# Sheet1.net
KiCad netlist of a schematic drawn in Altium Designer
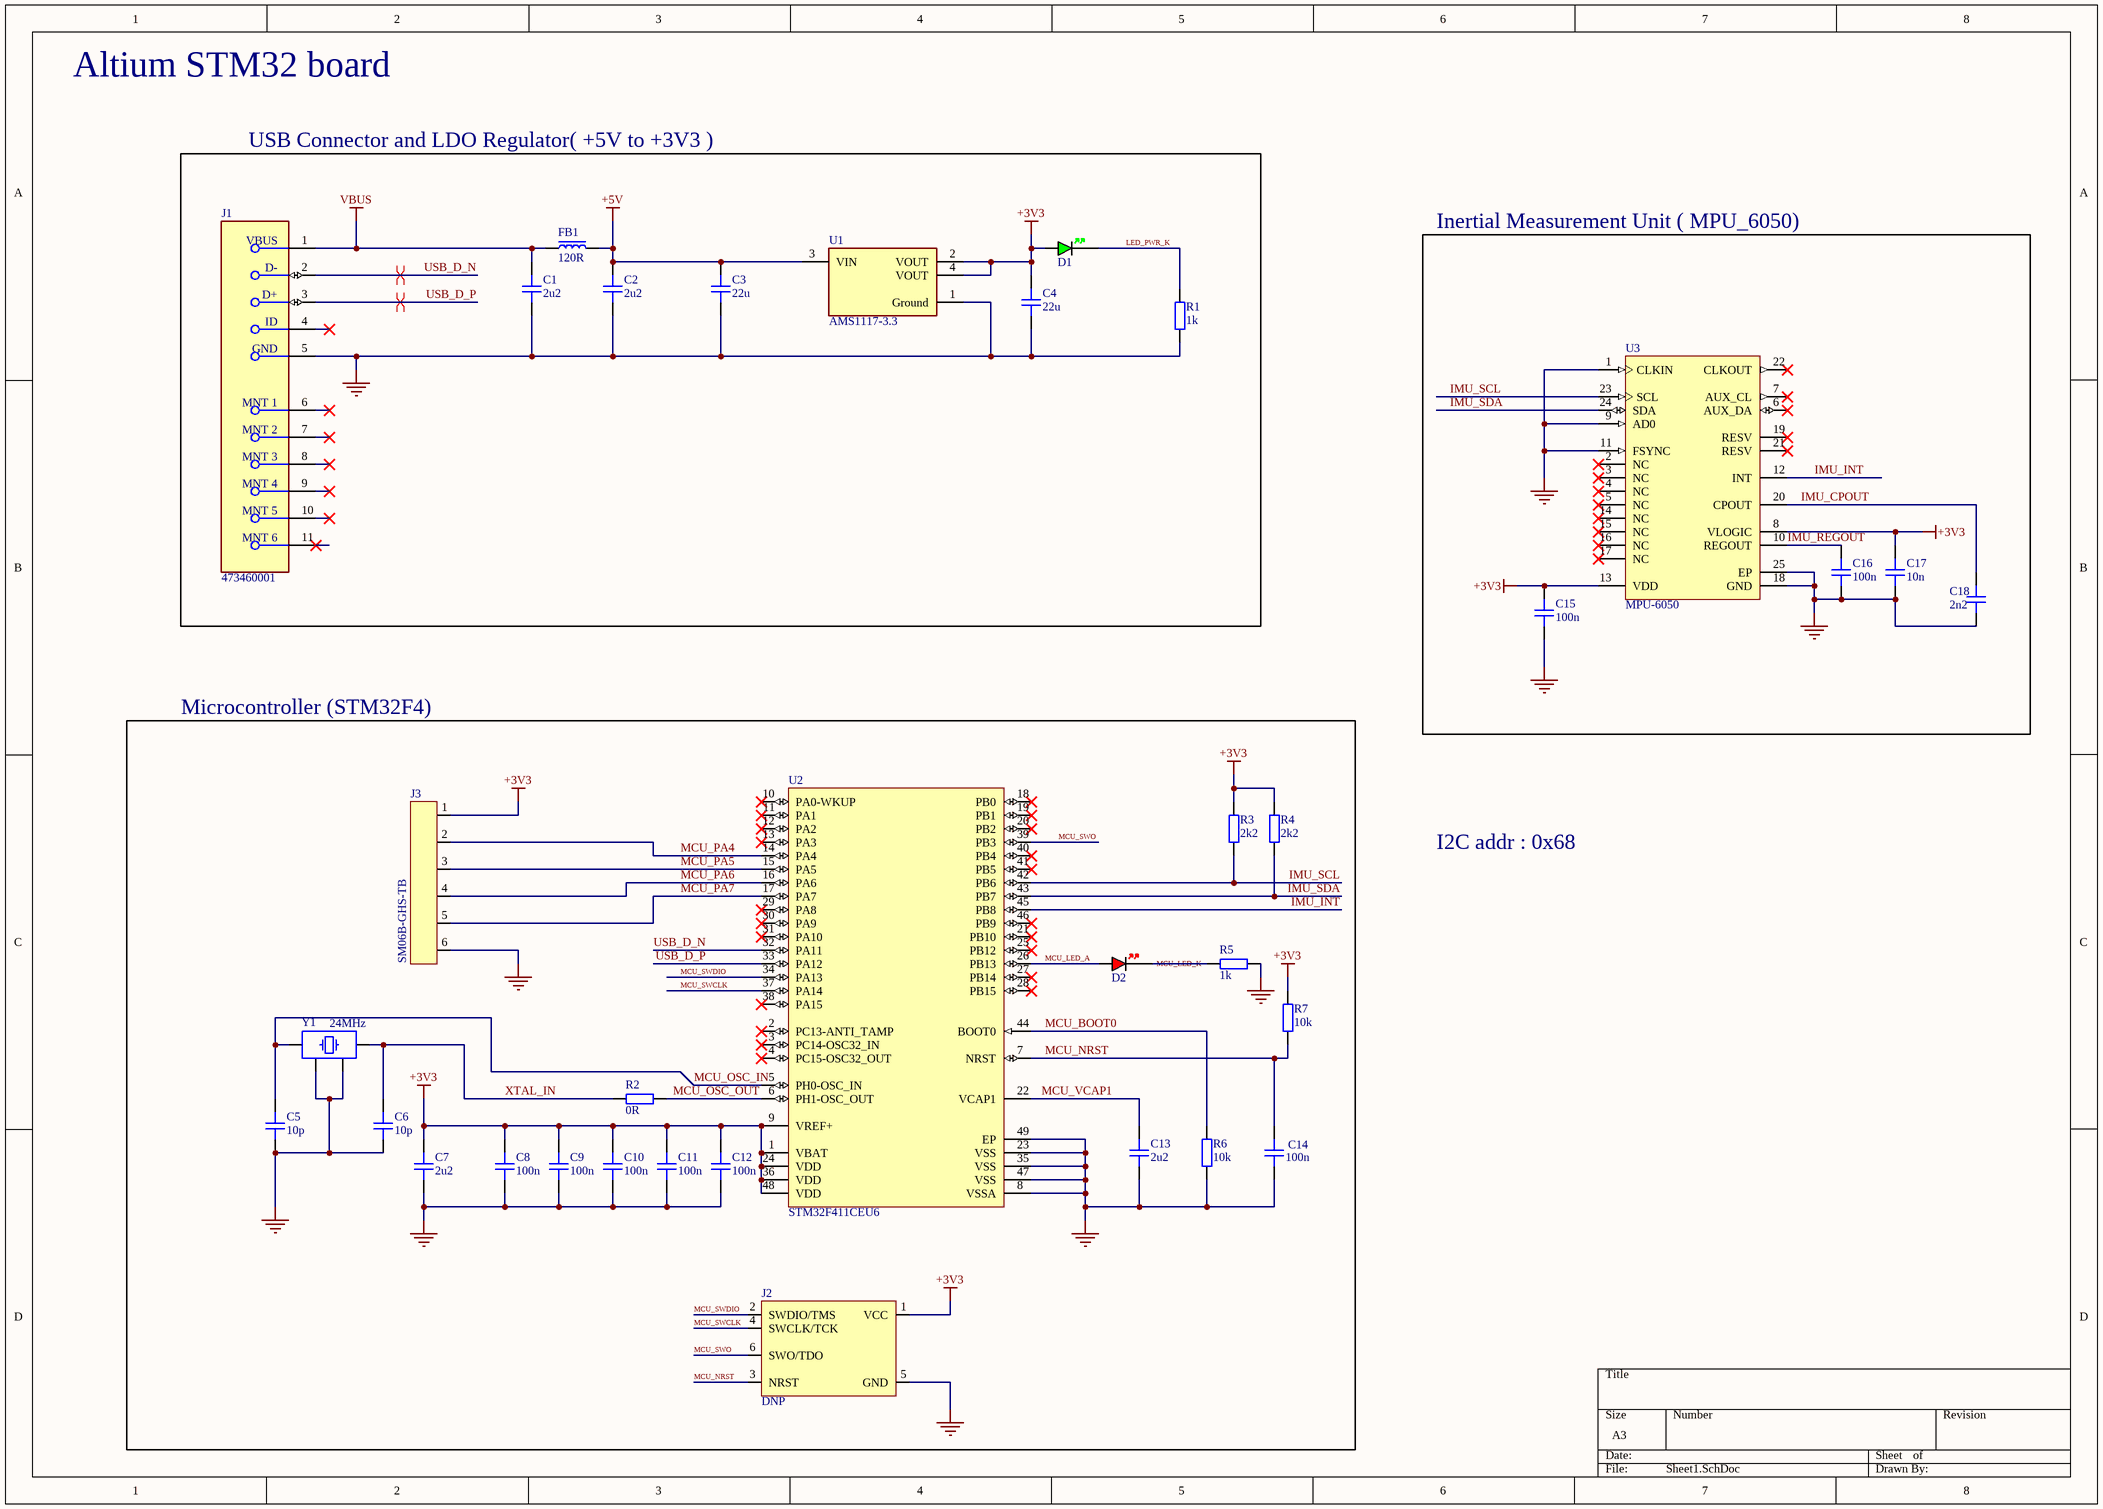
[diagram p0: Sheet1.SchDoc]

(export (version "E")
  (design (tool "Eeschema 10.0.6"))
  (components
    (comp (ref "C1")
      (value "2u2")
      (footprint "CAP_0603")
      (description "Capacitor SMD 0603")
      (libsource (lib "Schematic-Lib-PhilsLab") (part "CAP_0603"))
    )
    (comp (ref "C2")
      (value "2u2")
      (footprint "CAP_0603")
      (description "Capacitor SMD 0603")
      (libsource (lib "Schematic-Lib-PhilsLab") (part "CAP_0603"))
    )
    (comp (ref "C3")
      (value "22u")
      (footprint "CAP_0805")
      (description "Capacitor SMD 0805")
      (libsource (lib "Schematic-Lib-PhilsLab") (part "CAP_0805"))
    )
    (comp (ref "C4")
      (value "22u")
      (footprint "CAP_0805")
      (description "Capacitor SMD 0805")
      (libsource (lib "Schematic-Lib-PhilsLab") (part "CAP_0805"))
    )
    (comp (ref "C5")
      (value "10p")
      (footprint "CAP_0402")
      (description "Capacitor SMD 0402")
      (libsource (lib "Schematic-Lib-PhilsLab") (part "CAP_0402"))
    )
    (comp (ref "C6")
      (value "10p")
      (footprint "CAP_0402")
      (description "Capacitor SMD 0402")
      (libsource (lib "Schematic-Lib-PhilsLab") (part "CAP_0402"))
    )
    (comp (ref "C7")
      (value "2u2")
      (footprint "CAP_0603")
      (description "Capacitor SMD 0603")
      (libsource (lib "Schematic-Lib-PhilsLab") (part "CAP_0603"))
    )
    (comp (ref "C8")
      (value "100n")
      (footprint "CAP_0402")
      (description "Capacitor SMD 0402")
      (libsource (lib "Schematic-Lib-PhilsLab") (part "CAP_0402"))
    )
    (comp (ref "C9")
      (value "100n")
      (footprint "CAP_0402")
      (description "Capacitor SMD 0402")
      (libsource (lib "Schematic-Lib-PhilsLab") (part "CAP_0402"))
    )
    (comp (ref "C10")
      (value "100n")
      (footprint "CAP_0402")
      (description "Capacitor SMD 0402")
      (libsource (lib "Schematic-Lib-PhilsLab") (part "CAP_0402"))
    )
    (comp (ref "C11")
      (value "100n")
      (footprint "CAP_0402")
      (description "Capacitor SMD 0402")
      (libsource (lib "Schematic-Lib-PhilsLab") (part "CAP_0402"))
    )
    (comp (ref "C12")
      (value "100n")
      (footprint "CAP_0402")
      (description "Capacitor SMD 0402")
      (libsource (lib "Schematic-Lib-PhilsLab") (part "CAP_0402"))
    )
    (comp (ref "C13")
      (value "2u2")
      (footprint "CAP_0603")
      (description "Capacitor SMD 0603")
      (libsource (lib "Schematic-Lib-PhilsLab") (part "CAP_0603"))
    )
    (comp (ref "C14")
      (value "100n")
      (footprint "CAP_0402")
      (description "Capacitor SMD 0402")
      (libsource (lib "Schematic-Lib-PhilsLab") (part "CAP_0402"))
    )
    (comp (ref "C15")
      (value "100n")
      (footprint "CAP_0402")
      (description "Capacitor SMD 0402")
      (libsource (lib "Schematic-Lib-PhilsLab") (part "CAP_0402"))
    )
    (comp (ref "C16")
      (value "100n")
      (footprint "CAP_0402")
      (description "Capacitor SMD 0402")
      (libsource (lib "Schematic-Lib-PhilsLab") (part "CAP_0402"))
    )
    (comp (ref "C17")
      (value "10n")
      (footprint "CAP_0402")
      (description "Capacitor SMD 0402")
      (libsource (lib "Schematic-Lib-PhilsLab") (part "CAP_0402"))
    )
    (comp (ref "C18")
      (value "2n2")
      (footprint "CAP_0402")
      (description "Capacitor SMD 0402")
      (libsource (lib "Schematic-Lib-PhilsLab") (part "CAP_0402"))
    )
    (comp (ref "D1")
      (value "GREEN")
      (footprint "LED_0402_GREEN")
      (description "LED 0402 GREEN SMD")
      (libsource (lib "Schematic-Lib-PhilsLab") (part "LED_0402_GREEN"))
    )
    (comp (ref "D2")
      (value "RED")
      (footprint "LED_0402_RED")
      (description "LED 0402 RED SMD")
      (libsource (lib "Schematic-Lib-PhilsLab") (part "LED_0402_RED"))
    )
    (comp (ref "FB1")
      (value "120R")
      (footprint "FB_0603")
      (description "Ferrite Bead SMD 0603")
      (libsource (lib "Schematic-Lib-PhilsLab") (part "FB_0603"))
    )
    (comp (ref "J1")
      (value "473460001")
      (footprint "FP-473460001-MFG")
      (description "CONN RCPT USB2.0 MICRO B SMD R/A")
      (fields
        (field (name "OCTOPART") "https://octopart.com/47346-0001-molex-7164928")
        (field (name "MANUFACTURER") "Molex")
      )
      (libsource (lib "Altium Content Vault") (part "53ae1f1d9b557310b43ca686e5bb76a"))
    )
    (comp (ref "J2")
      (value "DNP")
      (footprint "TC2030-NL-FP")
      (description "Tag-Connect No-Solder SWD Debug Connector (No Legs) DO NOT PLACE")
      (fields
        (field (name "MANUFACTURER") "Tag-Connect")
        (field (name "MANUFACTURER PART NUMBER") "TC2030-NL-FP")
      )
      (libsource (lib "Schematic-Lib-PhilsLab") (part "TC2030-NL"))
    )
    (comp (ref "J3")
      (value "SM06B-GHS-TB")
      (footprint "SM06B-GHS-TB")
      (description "Header Connector 6 Position 1.25MM Pitch SMD Horizontal JST GH")
      (fields (field (name "MANUFACTURER") "JST"))
      (libsource (lib "Schematic-Lib-PhilsLab") (part "SM06B-GHS-TB"))
    )
    (comp (ref "R1")
      (value "1k")
      (footprint "RES_0402")
      (description "Resistor SMD 0402")
      (libsource (lib "Schematic-Lib-PhilsLab") (part "RES_0402"))
    )
    (comp (ref "R2")
      (value "0R")
      (footprint "RES_0402")
      (description "Resistor SMD 0402")
      (libsource (lib "Schematic-Lib-PhilsLab") (part "RES_0402"))
    )
    (comp (ref "R3")
      (value "2k2")
      (footprint "RES_0402")
      (description "Resistor SMD 0402")
      (libsource (lib "Schematic-Lib-PhilsLab") (part "RES_0402"))
    )
    (comp (ref "R4")
      (value "2k2")
      (footprint "RES_0402")
      (description "Resistor SMD 0402")
      (libsource (lib "Schematic-Lib-PhilsLab") (part "RES_0402"))
    )
    (comp (ref "R5")
      (value "1k")
      (footprint "RES_0402")
      (description "Resistor SMD 0402")
      (libsource (lib "Schematic-Lib-PhilsLab") (part "RES_0402"))
    )
    (comp (ref "R6")
      (value "10k")
      (footprint "RES_0402")
      (description "Resistor SMD 0402")
      (libsource (lib "Schematic-Lib-PhilsLab") (part "RES_0402"))
    )
    (comp (ref "R7")
      (value "10k")
      (footprint "RES_0402")
      (description "Resistor SMD 0402")
      (libsource (lib "Schematic-Lib-PhilsLab") (part "RES_0402"))
    )
    (comp (ref "U1")
      (value "AMS1117-3.3")
      (footprint "FP-AMS1117-IPC_C")
      (description "LDO Voltage Regulators 1A, 3.3V")
      (fields
        (field (name "OCTOPART") "https://octopart.com/ams1117-3.3-advanced+monolithic+systems-25899300")
        (field (name "MANUFACTURER") "Advanced Monolithic Systems")
      )
      (libsource (lib "Altium Content Vault") (part "8bdbb5f8e77002000e30dd2845d0354"))
    )
    (comp (ref "U2")
      (value "STM32F411CEU6")
      (footprint "STM-UFQFPN48_L")
      (libsource (lib "Altium Content Vault") (part "MC-ARM-STM32F411-UFQFPN48"))
    )
    (comp (ref "U3")
      (value "MPU-6050")
      (footprint "IS-QFN-24_V")
      (fields (field (name "MANUFACTURER") "InvenSense"))
      (libsource (lib "Altium Content Vault") (part "IS-MPU-6050-QFN-24"))
    )
    (comp (ref "Y1")
      (value "24MHz")
      (footprint "XTAL_3225")
      (description "Crystal SMD 24MHz 10PPM 7pF 3225")
      (fields
        (field (name "MANUFACTURER") "Epson")
        (field (name "MANUFACTURER PART NUMBER") "TSX-3225 24.0000MF15X-AC")
      )
      (libsource (lib "Schematic-Lib-PhilsLab") (part "TSX-3225_24.0000MF15X-AC"))
    )
  )
  (nets
    (net (code "1") (name "+3V3") (class "Default")
      (node (ref "C10") (pin "2") (pinfunction "2_2") (pintype "passive"))
      (node (ref "C11") (pin "2") (pinfunction "2_2") (pintype "passive"))
      (node (ref "C12") (pin "2") (pinfunction "2_2") (pintype "passive"))
      (node (ref "C15") (pin "2") (pinfunction "2_2") (pintype "passive"))
      (node (ref "C17") (pin "2") (pinfunction "2_2") (pintype "passive"))
      (node (ref "C4") (pin "2") (pinfunction "2_2") (pintype "passive"))
      (node (ref "C7") (pin "2") (pinfunction "2_2") (pintype "passive"))
      (node (ref "C8") (pin "2") (pinfunction "2_2") (pintype "passive"))
      (node (ref "C9") (pin "2") (pinfunction "2_2") (pintype "passive"))
      (node (ref "D1") (pin "A") (pinfunction "A_A") (pintype "passive"))
      (node (ref "J2") (pin "1") (pinfunction "VCC_1") (pintype "passive"))
      (node (ref "J3") (pin "1") (pinfunction "1_1") (pintype "passive"))
      (node (ref "R3") (pin "2") (pinfunction "2_2") (pintype "passive"))
      (node (ref "R4") (pin "2") (pinfunction "2_2") (pintype "passive"))
      (node (ref "R7") (pin "2") (pinfunction "2_2") (pintype "passive"))
      (node (ref "U1") (pin "2") (pinfunction "VOUT_2") (pintype "passive"))
      (node (ref "U1") (pin "4") (pinfunction "VOUT_4") (pintype "passive"))
      (node (ref "U2") (pin "1") (pinfunction "VBAT_1") (pintype "power_in"))
      (node (ref "U2") (pin "24") (pinfunction "VDD_24") (pintype "power_in"))
      (node (ref "U2") (pin "36") (pinfunction "VDD_36") (pintype "power_in"))
      (node (ref "U2") (pin "48") (pinfunction "VDD_48") (pintype "power_in"))
      (node (ref "U2") (pin "9") (pinfunction "VREF+_9") (pintype "power_in"))
      (node (ref "U3") (pin "13") (pinfunction "VDD_13") (pintype "power_in"))
      (node (ref "U3") (pin "8") (pinfunction "VLOGIC_8") (pintype "power_in"))
    )
    (net (code "2") (name "+5V") (class "Default")
      (node (ref "C2") (pin "2") (pinfunction "2_2") (pintype "passive"))
      (node (ref "C3") (pin "2") (pinfunction "2_2") (pintype "passive"))
      (node (ref "FB1") (pin "2") (pinfunction "2_2") (pintype "passive"))
      (node (ref "U1") (pin "3") (pinfunction "VIN_3") (pintype "power_in"))
    )
    (net (code "3") (name "/IMU_CPOUT") (class "Default")
      (node (ref "C18") (pin "2") (pinfunction "2_2") (pintype "passive"))
      (node (ref "U3") (pin "20") (pinfunction "CPOUT_20") (pintype "passive"))
    )
    (net (code "4") (name "/IMU_INT") (class "Default")
      (node (ref "U2") (pin "45") (pinfunction "PB8_45") (pintype "bidirectional"))
      (node (ref "U3") (pin "12") (pinfunction "INT_12") (pintype "open_collector"))
    )
    (net (code "5") (name "/IMU_REGOUT") (class "Default")
      (node (ref "C16") (pin "2") (pinfunction "2_2") (pintype "passive"))
      (node (ref "U3") (pin "10") (pinfunction "REGOUT_10") (pintype "passive"))
    )
    (net (code "6") (name "/IMU_SCL") (class "Default")
      (node (ref "R3") (pin "1") (pinfunction "1_1") (pintype "passive"))
      (node (ref "U2") (pin "42") (pinfunction "PB6_42") (pintype "bidirectional"))
      (node (ref "U3") (pin "23") (pinfunction "SCL_23") (pintype "input"))
    )
    (net (code "7") (name "/IMU_SDA") (class "Default")
      (node (ref "R4") (pin "1") (pinfunction "1_1") (pintype "passive"))
      (node (ref "U2") (pin "43") (pinfunction "PB7_43") (pintype "bidirectional"))
      (node (ref "U3") (pin "24") (pinfunction "SDA_24") (pintype "bidirectional"))
    )
    (net (code "8") (name "/LED_PWR_K") (class "Default")
      (node (ref "D1") (pin "K") (pinfunction "K_K") (pintype "passive"))
      (node (ref "R1") (pin "2") (pinfunction "2_2") (pintype "passive"))
    )
    (net (code "9") (name "/MCU_BOOT0") (class "Default")
      (node (ref "R6") (pin "2") (pinfunction "2_2") (pintype "passive"))
      (node (ref "U2") (pin "44") (pinfunction "BOOT0_44") (pintype "input"))
    )
    (net (code "10") (name "/MCU_LED_A") (class "Default")
      (node (ref "D2") (pin "A") (pinfunction "A_A") (pintype "passive"))
      (node (ref "U2") (pin "26") (pinfunction "PB13_26") (pintype "bidirectional"))
    )
    (net (code "11") (name "/MCU_LED_K") (class "Default")
      (node (ref "D2") (pin "K") (pinfunction "K_K") (pintype "passive"))
      (node (ref "R5") (pin "2") (pinfunction "2_2") (pintype "passive"))
    )
    (net (code "12") (name "/MCU_NRST") (class "Default")
      (node (ref "C14") (pin "2") (pinfunction "2_2") (pintype "passive"))
      (node (ref "J2") (pin "3") (pinfunction "NRST_3") (pintype "passive"))
      (node (ref "R7") (pin "1") (pinfunction "1_1") (pintype "passive"))
      (node (ref "U2") (pin "7") (pinfunction "NRST_7") (pintype "bidirectional"))
    )
    (net (code "13") (name "/MCU_OSC_IN") (class "Default")
      (node (ref "C5") (pin "2") (pinfunction "2_2") (pintype "passive"))
      (node (ref "U2") (pin "5") (pinfunction "PH0-OSC_IN_5") (pintype "bidirectional"))
      (node (ref "Y1") (pin "1") (pinfunction "1_1") (pintype "passive"))
    )
    (net (code "14") (name "/MCU_OSC_OUT") (class "Default")
      (node (ref "R2") (pin "2") (pinfunction "2_2") (pintype "passive"))
      (node (ref "U2") (pin "6") (pinfunction "PH1-OSC_OUT_6") (pintype "bidirectional"))
    )
    (net (code "15") (name "/MCU_PA4") (class "Default")
      (node (ref "J3") (pin "2") (pinfunction "2_2") (pintype "passive"))
      (node (ref "U2") (pin "14") (pinfunction "PA4_14") (pintype "bidirectional"))
    )
    (net (code "16") (name "/MCU_PA5") (class "Default")
      (node (ref "J3") (pin "3") (pinfunction "3_3") (pintype "passive"))
      (node (ref "U2") (pin "15") (pinfunction "PA5_15") (pintype "bidirectional"))
    )
    (net (code "17") (name "/MCU_PA6") (class "Default")
      (node (ref "J3") (pin "4") (pinfunction "4_4") (pintype "passive"))
      (node (ref "U2") (pin "16") (pinfunction "PA6_16") (pintype "bidirectional"))
    )
    (net (code "18") (name "/MCU_PA7") (class "Default")
      (node (ref "J3") (pin "5") (pinfunction "5_5") (pintype "passive"))
      (node (ref "U2") (pin "17") (pinfunction "PA7_17") (pintype "bidirectional"))
    )
    (net (code "19") (name "/MCU_SWCLK") (class "Default")
      (node (ref "J2") (pin "4") (pinfunction "SWCLK/TCK_4") (pintype "passive"))
      (node (ref "U2") (pin "37") (pinfunction "PA14_37") (pintype "bidirectional"))
    )
    (net (code "20") (name "/MCU_SWDIO") (class "Default")
      (node (ref "J2") (pin "2") (pinfunction "SWDIO/TMS_2") (pintype "passive"))
      (node (ref "U2") (pin "34") (pinfunction "PA13_34") (pintype "bidirectional"))
    )
    (net (code "21") (name "/MCU_SWO") (class "Default")
      (node (ref "J2") (pin "6") (pinfunction "SWO/TDO_6") (pintype "passive"))
      (node (ref "U2") (pin "39") (pinfunction "PB3_39") (pintype "bidirectional"))
    )
    (net (code "22") (name "/MCU_VCAP1") (class "Default")
      (node (ref "C13") (pin "2") (pinfunction "2_2") (pintype "passive"))
      (node (ref "U2") (pin "22") (pinfunction "VCAP1_22") (pintype "passive"))
    )
    (net (code "23") (name "/USB_D_N") (class "Default")
      (node (ref "J1") (pin "2") (pinfunction "D-_2") (pintype "bidirectional"))
      (node (ref "U2") (pin "32") (pinfunction "PA11_32") (pintype "bidirectional"))
    )
    (net (code "24") (name "/USB_D_P") (class "Default")
      (node (ref "J1") (pin "3") (pinfunction "D+_3") (pintype "bidirectional"))
      (node (ref "U2") (pin "33") (pinfunction "PA12_33") (pintype "bidirectional"))
    )
    (net (code "25") (name "/XTAL_IN") (class "Default")
      (node (ref "C6") (pin "2") (pinfunction "2_2") (pintype "passive"))
      (node (ref "R2") (pin "1") (pinfunction "1_1") (pintype "passive"))
      (node (ref "Y1") (pin "3") (pinfunction "3_3") (pintype "passive"))
    )
    (net (code "26") (name "GND") (class "Default")
      (node (ref "C1") (pin "1") (pinfunction "1_1") (pintype "passive"))
      (node (ref "C10") (pin "1") (pinfunction "1_1") (pintype "passive"))
      (node (ref "C11") (pin "1") (pinfunction "1_1") (pintype "passive"))
      (node (ref "C12") (pin "1") (pinfunction "1_1") (pintype "passive"))
      (node (ref "C13") (pin "1") (pinfunction "1_1") (pintype "passive"))
      (node (ref "C14") (pin "1") (pinfunction "1_1") (pintype "passive"))
      (node (ref "C15") (pin "1") (pinfunction "1_1") (pintype "passive"))
      (node (ref "C16") (pin "1") (pinfunction "1_1") (pintype "passive"))
      (node (ref "C17") (pin "1") (pinfunction "1_1") (pintype "passive"))
      (node (ref "C18") (pin "1") (pinfunction "1_1") (pintype "passive"))
      (node (ref "C2") (pin "1") (pinfunction "1_1") (pintype "passive"))
      (node (ref "C3") (pin "1") (pinfunction "1_1") (pintype "passive"))
      (node (ref "C4") (pin "1") (pinfunction "1_1") (pintype "passive"))
      (node (ref "C5") (pin "1") (pinfunction "1_1") (pintype "passive"))
      (node (ref "C6") (pin "1") (pinfunction "1_1") (pintype "passive"))
      (node (ref "C7") (pin "1") (pinfunction "1_1") (pintype "passive"))
      (node (ref "C8") (pin "1") (pinfunction "1_1") (pintype "passive"))
      (node (ref "C9") (pin "1") (pinfunction "1_1") (pintype "passive"))
      (node (ref "J1") (pin "5") (pinfunction "GND_5") (pintype "power_in"))
      (node (ref "J2") (pin "5") (pinfunction "GND_5") (pintype "passive"))
      (node (ref "J3") (pin "6") (pinfunction "6_6") (pintype "passive"))
      (node (ref "R1") (pin "1") (pinfunction "1_1") (pintype "passive"))
      (node (ref "R5") (pin "1") (pinfunction "1_1") (pintype "passive"))
      (node (ref "R6") (pin "1") (pinfunction "1_1") (pintype "passive"))
      (node (ref "U1") (pin "1") (pinfunction "Ground_1") (pintype "power_in"))
      (node (ref "U2") (pin "23") (pinfunction "VSS_23") (pintype "power_in"))
      (node (ref "U2") (pin "35") (pinfunction "VSS_35") (pintype "power_in"))
      (node (ref "U2") (pin "47") (pinfunction "VSS_47") (pintype "power_in"))
      (node (ref "U2") (pin "49") (pinfunction "EP_49") (pintype "power_in"))
      (node (ref "U2") (pin "8") (pinfunction "VSSA_8") (pintype "power_in"))
      (node (ref "U3") (pin "1") (pinfunction "CLKIN_1") (pintype "input"))
      (node (ref "U3") (pin "11") (pinfunction "FSYNC_11") (pintype "input"))
      (node (ref "U3") (pin "18") (pinfunction "GND_18") (pintype "power_in"))
      (node (ref "U3") (pin "25") (pinfunction "EP_25") (pintype "power_in"))
      (node (ref "U3") (pin "9") (pinfunction "AD0_9") (pintype "input"))
      (node (ref "Y1") (pin "2") (pinfunction "2_2") (pintype "passive"))
      (node (ref "Y1") (pin "4") (pinfunction "4_4") (pintype "passive"))
    )
    (net (code "27") (name "VBUS") (class "Default")
      (node (ref "C1") (pin "2") (pinfunction "2_2") (pintype "passive"))
      (node (ref "FB1") (pin "1") (pinfunction "1_1") (pintype "passive"))
      (node (ref "J1") (pin "1") (pinfunction "VBUS_1") (pintype "power_in"))
    )
    (net (code "28") (name "unconnected-(J1-ID-Pad4)") (class "Default")
      (node (ref "J1") (pin "4") (pinfunction "ID_4") (pintype "passive+no_connect"))
    )
    (net (code "29") (name "unconnected-(J1-MNT_1-Pad6)") (class "Default")
      (node (ref "J1") (pin "6") (pinfunction "MNT_1_6") (pintype "passive+no_connect"))
    )
    (net (code "30") (name "unconnected-(J1-MNT_2-Pad7)") (class "Default")
      (node (ref "J1") (pin "7") (pinfunction "MNT_2_7") (pintype "passive+no_connect"))
    )
    (net (code "31") (name "unconnected-(J1-MNT_3-Pad8)") (class "Default")
      (node (ref "J1") (pin "8") (pinfunction "MNT_3_8") (pintype "passive+no_connect"))
    )
    (net (code "32") (name "unconnected-(J1-MNT_4-Pad9)") (class "Default")
      (node (ref "J1") (pin "9") (pinfunction "MNT_4_9") (pintype "passive+no_connect"))
    )
    (net (code "33") (name "unconnected-(J1-MNT_5-Pad10)") (class "Default")
      (node (ref "J1") (pin "10") (pinfunction "MNT_5_10") (pintype "passive+no_connect"))
    )
    (net (code "34") (name "unconnected-(J1-MNT_6-Pad11)") (class "Default")
      (node (ref "J1") (pin "11") (pinfunction "MNT_6_11") (pintype "passive+no_connect"))
    )
    (net (code "35") (name "unconnected-(U2-PA0-WKUP-Pad10)") (class "Default")
      (node (ref "U2") (pin "10") (pinfunction "PA0-WKUP_10") (pintype "bidirectional+no_connect"))
    )
    (net (code "36") (name "unconnected-(U2-PA1-Pad11)") (class "Default")
      (node (ref "U2") (pin "11") (pinfunction "PA1_11") (pintype "bidirectional+no_connect"))
    )
    (net (code "37") (name "unconnected-(U2-PA2-Pad12)") (class "Default")
      (node (ref "U2") (pin "12") (pinfunction "PA2_12") (pintype "bidirectional+no_connect"))
    )
    (net (code "38") (name "unconnected-(U2-PA3-Pad13)") (class "Default")
      (node (ref "U2") (pin "13") (pinfunction "PA3_13") (pintype "bidirectional+no_connect"))
    )
    (net (code "39") (name "unconnected-(U2-PA8-Pad29)") (class "Default")
      (node (ref "U2") (pin "29") (pinfunction "PA8_29") (pintype "bidirectional+no_connect"))
    )
    (net (code "40") (name "unconnected-(U2-PA9-Pad30)") (class "Default")
      (node (ref "U2") (pin "30") (pinfunction "PA9_30") (pintype "bidirectional+no_connect"))
    )
    (net (code "41") (name "unconnected-(U2-PA10-Pad31)") (class "Default")
      (node (ref "U2") (pin "31") (pinfunction "PA10_31") (pintype "bidirectional+no_connect"))
    )
    (net (code "42") (name "unconnected-(U2-PA15-Pad38)") (class "Default")
      (node (ref "U2") (pin "38") (pinfunction "PA15_38") (pintype "bidirectional+no_connect"))
    )
    (net (code "43") (name "unconnected-(U2-PB0-Pad18)") (class "Default")
      (node (ref "U2") (pin "18") (pinfunction "PB0_18") (pintype "bidirectional+no_connect"))
    )
    (net (code "44") (name "unconnected-(U2-PB1-Pad19)") (class "Default")
      (node (ref "U2") (pin "19") (pinfunction "PB1_19") (pintype "bidirectional+no_connect"))
    )
    (net (code "45") (name "unconnected-(U2-PB2-Pad20)") (class "Default")
      (node (ref "U2") (pin "20") (pinfunction "PB2_20") (pintype "bidirectional+no_connect"))
    )
    (net (code "46") (name "unconnected-(U2-PB4-Pad40)") (class "Default")
      (node (ref "U2") (pin "40") (pinfunction "PB4_40") (pintype "bidirectional+no_connect"))
    )
    (net (code "47") (name "unconnected-(U2-PB5-Pad41)") (class "Default")
      (node (ref "U2") (pin "41") (pinfunction "PB5_41") (pintype "bidirectional+no_connect"))
    )
    (net (code "48") (name "unconnected-(U2-PB9-Pad46)") (class "Default")
      (node (ref "U2") (pin "46") (pinfunction "PB9_46") (pintype "bidirectional+no_connect"))
    )
    (net (code "49") (name "unconnected-(U2-PB10-Pad21)") (class "Default")
      (node (ref "U2") (pin "21") (pinfunction "PB10_21") (pintype "bidirectional+no_connect"))
    )
    (net (code "50") (name "unconnected-(U2-PB12-Pad25)") (class "Default")
      (node (ref "U2") (pin "25") (pinfunction "PB12_25") (pintype "bidirectional+no_connect"))
    )
    (net (code "51") (name "unconnected-(U2-PB14-Pad27)") (class "Default")
      (node (ref "U2") (pin "27") (pinfunction "PB14_27") (pintype "bidirectional+no_connect"))
    )
    (net (code "52") (name "unconnected-(U2-PB15-Pad28)") (class "Default")
      (node (ref "U2") (pin "28") (pinfunction "PB15_28") (pintype "bidirectional+no_connect"))
    )
    (net (code "53") (name "unconnected-(U2-PC13-ANTI_TAMP-Pad2)") (class "Default")
      (node (ref "U2") (pin "2") (pinfunction "PC13-ANTI_TAMP_2") (pintype "bidirectional+no_connect"))
    )
    (net (code "54") (name "unconnected-(U2-PC14-OSC32_IN-Pad3)") (class "Default")
      (node (ref "U2") (pin "3") (pinfunction "PC14-OSC32_IN_3") (pintype "bidirectional+no_connect"))
    )
    (net (code "55") (name "unconnected-(U2-PC15-OSC32_OUT-Pad4)") (class "Default")
      (node (ref "U2") (pin "4") (pinfunction "PC15-OSC32_OUT_4") (pintype "bidirectional+no_connect"))
    )
    (net (code "56") (name "unconnected-(U3-AUX_CL-Pad7)") (class "Default")
      (node (ref "U3") (pin "7") (pinfunction "AUX_CL_7") (pintype "output+no_connect"))
    )
    (net (code "57") (name "unconnected-(U3-AUX_DA-Pad6)") (class "Default")
      (node (ref "U3") (pin "6") (pinfunction "AUX_DA_6") (pintype "bidirectional+no_connect"))
    )
    (net (code "58") (name "unconnected-(U3-CLKOUT-Pad22)") (class "Default")
      (node (ref "U3") (pin "22") (pinfunction "CLKOUT_22") (pintype "output+no_connect"))
    )
    (net (code "59") (name "unconnected-(U3-NC-Pad2)") (class "Default")
      (node (ref "U3") (pin "2") (pinfunction "NC_2") (pintype "passive+no_connect"))
    )
    (net (code "60") (name "unconnected-(U3-NC-Pad3)") (class "Default")
      (node (ref "U3") (pin "3") (pinfunction "NC_3") (pintype "passive+no_connect"))
    )
    (net (code "61") (name "unconnected-(U3-NC-Pad4)") (class "Default")
      (node (ref "U3") (pin "4") (pinfunction "NC_4") (pintype "passive+no_connect"))
    )
    (net (code "62") (name "unconnected-(U3-NC-Pad5)") (class "Default")
      (node (ref "U3") (pin "5") (pinfunction "NC_5") (pintype "passive+no_connect"))
    )
    (net (code "63") (name "unconnected-(U3-NC-Pad14)") (class "Default")
      (node (ref "U3") (pin "14") (pinfunction "NC_14") (pintype "passive+no_connect"))
    )
    (net (code "64") (name "unconnected-(U3-NC-Pad15)") (class "Default")
      (node (ref "U3") (pin "15") (pinfunction "NC_15") (pintype "passive+no_connect"))
    )
    (net (code "65") (name "unconnected-(U3-NC-Pad16)") (class "Default")
      (node (ref "U3") (pin "16") (pinfunction "NC_16") (pintype "passive+no_connect"))
    )
    (net (code "66") (name "unconnected-(U3-NC-Pad17)") (class "Default")
      (node (ref "U3") (pin "17") (pinfunction "NC_17") (pintype "passive+no_connect"))
    )
    (net (code "67") (name "unconnected-(U3-RESV-Pad19)") (class "Default")
      (node (ref "U3") (pin "19") (pinfunction "RESV_19") (pintype "passive+no_connect"))
    )
    (net (code "68") (name "unconnected-(U3-RESV-Pad21)") (class "Default")
      (node (ref "U3") (pin "21") (pinfunction "RESV_21") (pintype "passive+no_connect"))
    )
  )
)
